# lightbulb_with_pwm.net
KiCad netlist of a schematic drawn in EAGLE
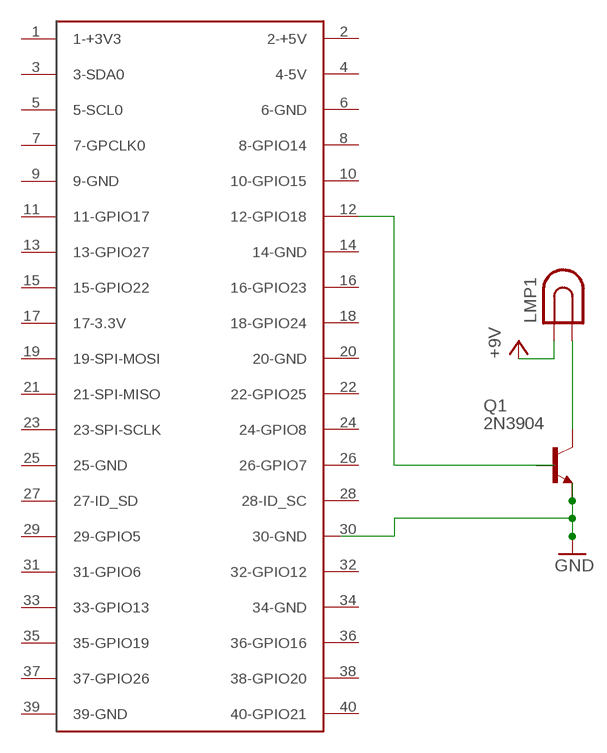
[diagram p0: schematic, sheet 1]

(export (version "E")
  (design (tool "Eeschema 10.0.6"))
  (components
    (comp (ref "LMP1")
      (value "LAMP")
      (footprint "eagle-import:LDH-5R")
      (libsource (lib "eagle-import") (part "LAMP"))
    )
    (comp (ref "Q1")
      (value "2N3904")
      (footprint "eagle-import:TO92")
      (libsource (lib "eagle-import") (part "2N3904"))
    )
    (comp (ref "U$2")
      (value "RASPBERRY-PI")
      (footprint "eagle-import:RASPBERRY-PI")
      (libsource (lib "eagle-import") (part "RASPBERRY-PI"))
    )
  )
  (nets
    (net (code "1") (name "+9V") (class "Default")
      (node (ref "LMP1") (pin "1") (pinfunction "1_1") (pintype "passive"))
    )
    (net (code "2") (name "GND") (class "Default")
      (node (ref "Q1") (pin "3") (pinfunction "E_3") (pintype "passive"))
    )
    (net (code "3") (name "Net-(Q1-C)") (class "Default")
      (node (ref "LMP1") (pin "2") (pinfunction "2_2") (pintype "passive"))
      (node (ref "Q1") (pin "1") (pinfunction "C_1") (pintype "passive"))
    )
    (net (code "4") (name "unconnected-(Q1-B-Pad2)") (class "Default")
      (node (ref "Q1") (pin "2") (pinfunction "B_2") (pintype "passive"))
    )
    (net (code "5") (name "unconnected-(U$2-1-+3V3-Pad1)") (class "Default")
      (node (ref "U$2") (pin "1") (pinfunction "1-+3V3_1") (pintype "bidirectional"))
    )
    (net (code "6") (name "unconnected-(U$2-2-+5V-Pad2)") (class "Default")
      (node (ref "U$2") (pin "2") (pinfunction "2-+5V_2") (pintype "bidirectional"))
    )
    (net (code "7") (name "unconnected-(U$2-3-SDA0-Pad3)") (class "Default")
      (node (ref "U$2") (pin "3") (pinfunction "3-SDA0_3") (pintype "bidirectional"))
    )
    (net (code "8") (name "unconnected-(U$2-4-5V-Pad4)") (class "Default")
      (node (ref "U$2") (pin "4") (pinfunction "4-5V_4") (pintype "bidirectional"))
    )
    (net (code "9") (name "unconnected-(U$2-5-SCL0-Pad5)") (class "Default")
      (node (ref "U$2") (pin "5") (pinfunction "5-SCL0_5") (pintype "bidirectional"))
    )
    (net (code "10") (name "unconnected-(U$2-6-GND-Pad6)") (class "Default")
      (node (ref "U$2") (pin "6") (pinfunction "6-GND_6") (pintype "bidirectional"))
    )
    (net (code "11") (name "unconnected-(U$2-7-GPCLK0-Pad7)") (class "Default")
      (node (ref "U$2") (pin "7") (pinfunction "7-GPCLK0_7") (pintype "bidirectional"))
    )
    (net (code "12") (name "unconnected-(U$2-8-GPIO14-Pad8)") (class "Default")
      (node (ref "U$2") (pin "8") (pinfunction "8-GPIO14_8") (pintype "bidirectional"))
    )
    (net (code "13") (name "unconnected-(U$2-9-GND-Pad9)") (class "Default")
      (node (ref "U$2") (pin "9") (pinfunction "9-GND_9") (pintype "bidirectional"))
    )
    (net (code "14") (name "unconnected-(U$2-10-GPIO15-Pad10)") (class "Default")
      (node (ref "U$2") (pin "10") (pinfunction "10-GPIO15_10") (pintype "bidirectional"))
    )
    (net (code "15") (name "unconnected-(U$2-11-GPIO17-Pad11)") (class "Default")
      (node (ref "U$2") (pin "11") (pinfunction "11-GPIO17_11") (pintype "bidirectional"))
    )
    (net (code "16") (name "unconnected-(U$2-12-GPIO18-Pad12)") (class "Default")
      (node (ref "U$2") (pin "12") (pinfunction "12-GPIO18_12") (pintype "bidirectional"))
    )
    (net (code "17") (name "unconnected-(U$2-13-GPIO27-Pad13)") (class "Default")
      (node (ref "U$2") (pin "13") (pinfunction "13-GPIO27_13") (pintype "bidirectional"))
    )
    (net (code "18") (name "unconnected-(U$2-14-GND-Pad14)") (class "Default")
      (node (ref "U$2") (pin "14") (pinfunction "14-GND_14") (pintype "bidirectional"))
    )
    (net (code "19") (name "unconnected-(U$2-15-GPIO22-Pad15)") (class "Default")
      (node (ref "U$2") (pin "15") (pinfunction "15-GPIO22_15") (pintype "bidirectional"))
    )
    (net (code "20") (name "unconnected-(U$2-16-GPIO23-Pad16)") (class "Default")
      (node (ref "U$2") (pin "16") (pinfunction "16-GPIO23_16") (pintype "bidirectional"))
    )
    (net (code "21") (name "unconnected-(U$2-17-3.3V-Pad17)") (class "Default")
      (node (ref "U$2") (pin "17") (pinfunction "17-3.3V_17") (pintype "bidirectional"))
    )
    (net (code "22") (name "unconnected-(U$2-18-GPIO24-Pad18)") (class "Default")
      (node (ref "U$2") (pin "18") (pinfunction "18-GPIO24_18") (pintype "bidirectional"))
    )
    (net (code "23") (name "unconnected-(U$2-19-SPI-MOSI-Pad19)") (class "Default")
      (node (ref "U$2") (pin "19") (pinfunction "19-SPI-MOSI_19") (pintype "bidirectional"))
    )
    (net (code "24") (name "unconnected-(U$2-20-GND-Pad20)") (class "Default")
      (node (ref "U$2") (pin "20") (pinfunction "20-GND_20") (pintype "bidirectional"))
    )
    (net (code "25") (name "unconnected-(U$2-21-SPI-MISO-Pad21)") (class "Default")
      (node (ref "U$2") (pin "21") (pinfunction "21-SPI-MISO_21") (pintype "bidirectional"))
    )
    (net (code "26") (name "unconnected-(U$2-22-GPIO25-Pad22)") (class "Default")
      (node (ref "U$2") (pin "22") (pinfunction "22-GPIO25_22") (pintype "bidirectional"))
    )
    (net (code "27") (name "unconnected-(U$2-23-SPI-SCLK-Pad23)") (class "Default")
      (node (ref "U$2") (pin "23") (pinfunction "23-SPI-SCLK_23") (pintype "bidirectional"))
    )
    (net (code "28") (name "unconnected-(U$2-24-GPIO8-Pad24)") (class "Default")
      (node (ref "U$2") (pin "24") (pinfunction "24-GPIO8_24") (pintype "bidirectional"))
    )
    (net (code "29") (name "unconnected-(U$2-25-GND-Pad25)") (class "Default")
      (node (ref "U$2") (pin "25") (pinfunction "25-GND_25") (pintype "bidirectional"))
    )
    (net (code "30") (name "unconnected-(U$2-26-GPIO7-Pad26)") (class "Default")
      (node (ref "U$2") (pin "26") (pinfunction "26-GPIO7_26") (pintype "bidirectional"))
    )
    (net (code "31") (name "unconnected-(U$2-27-ID_SD-Pad27)") (class "Default")
      (node (ref "U$2") (pin "27") (pinfunction "27-ID_SD_27") (pintype "bidirectional"))
    )
    (net (code "32") (name "unconnected-(U$2-28-ID_SC-Pad28)") (class "Default")
      (node (ref "U$2") (pin "28") (pinfunction "28-ID_SC_28") (pintype "bidirectional"))
    )
    (net (code "33") (name "unconnected-(U$2-29-GPIO5-Pad29)") (class "Default")
      (node (ref "U$2") (pin "29") (pinfunction "29-GPIO5_29") (pintype "bidirectional"))
    )
    (net (code "34") (name "unconnected-(U$2-30-GND-Pad30)") (class "Default")
      (node (ref "U$2") (pin "30") (pinfunction "30-GND_30") (pintype "bidirectional"))
    )
    (net (code "35") (name "unconnected-(U$2-31-GPIO6-Pad31)") (class "Default")
      (node (ref "U$2") (pin "31") (pinfunction "31-GPIO6_31") (pintype "bidirectional"))
    )
    (net (code "36") (name "unconnected-(U$2-32-GPIO12-Pad32)") (class "Default")
      (node (ref "U$2") (pin "32") (pinfunction "32-GPIO12_32") (pintype "bidirectional"))
    )
    (net (code "37") (name "unconnected-(U$2-33-GPIO13-Pad33)") (class "Default")
      (node (ref "U$2") (pin "33") (pinfunction "33-GPIO13_33") (pintype "bidirectional"))
    )
    (net (code "38") (name "unconnected-(U$2-34-GND-Pad34)") (class "Default")
      (node (ref "U$2") (pin "34") (pinfunction "34-GND_34") (pintype "bidirectional"))
    )
    (net (code "39") (name "unconnected-(U$2-35-GPIO19-Pad35)") (class "Default")
      (node (ref "U$2") (pin "35") (pinfunction "35-GPIO19_35") (pintype "bidirectional"))
    )
    (net (code "40") (name "unconnected-(U$2-36-GPIO16-Pad36)") (class "Default")
      (node (ref "U$2") (pin "36") (pinfunction "36-GPIO16_36") (pintype "bidirectional"))
    )
    (net (code "41") (name "unconnected-(U$2-37-GPIO26-Pad37)") (class "Default")
      (node (ref "U$2") (pin "37") (pinfunction "37-GPIO26_37") (pintype "bidirectional"))
    )
    (net (code "42") (name "unconnected-(U$2-38-GPIO20-Pad38)") (class "Default")
      (node (ref "U$2") (pin "38") (pinfunction "38-GPIO20_38") (pintype "bidirectional"))
    )
    (net (code "43") (name "unconnected-(U$2-39-GND-Pad39)") (class "Default")
      (node (ref "U$2") (pin "39") (pinfunction "39-GND_39") (pintype "bidirectional"))
    )
    (net (code "44") (name "unconnected-(U$2-40-GPIO21-Pad40)") (class "Default")
      (node (ref "U$2") (pin "40") (pinfunction "40-GPIO21_40") (pintype "bidirectional"))
    )
  )
)
